# exBoard_3.net
KiCad netlist of a schematic drawn in EasyEDA Pro
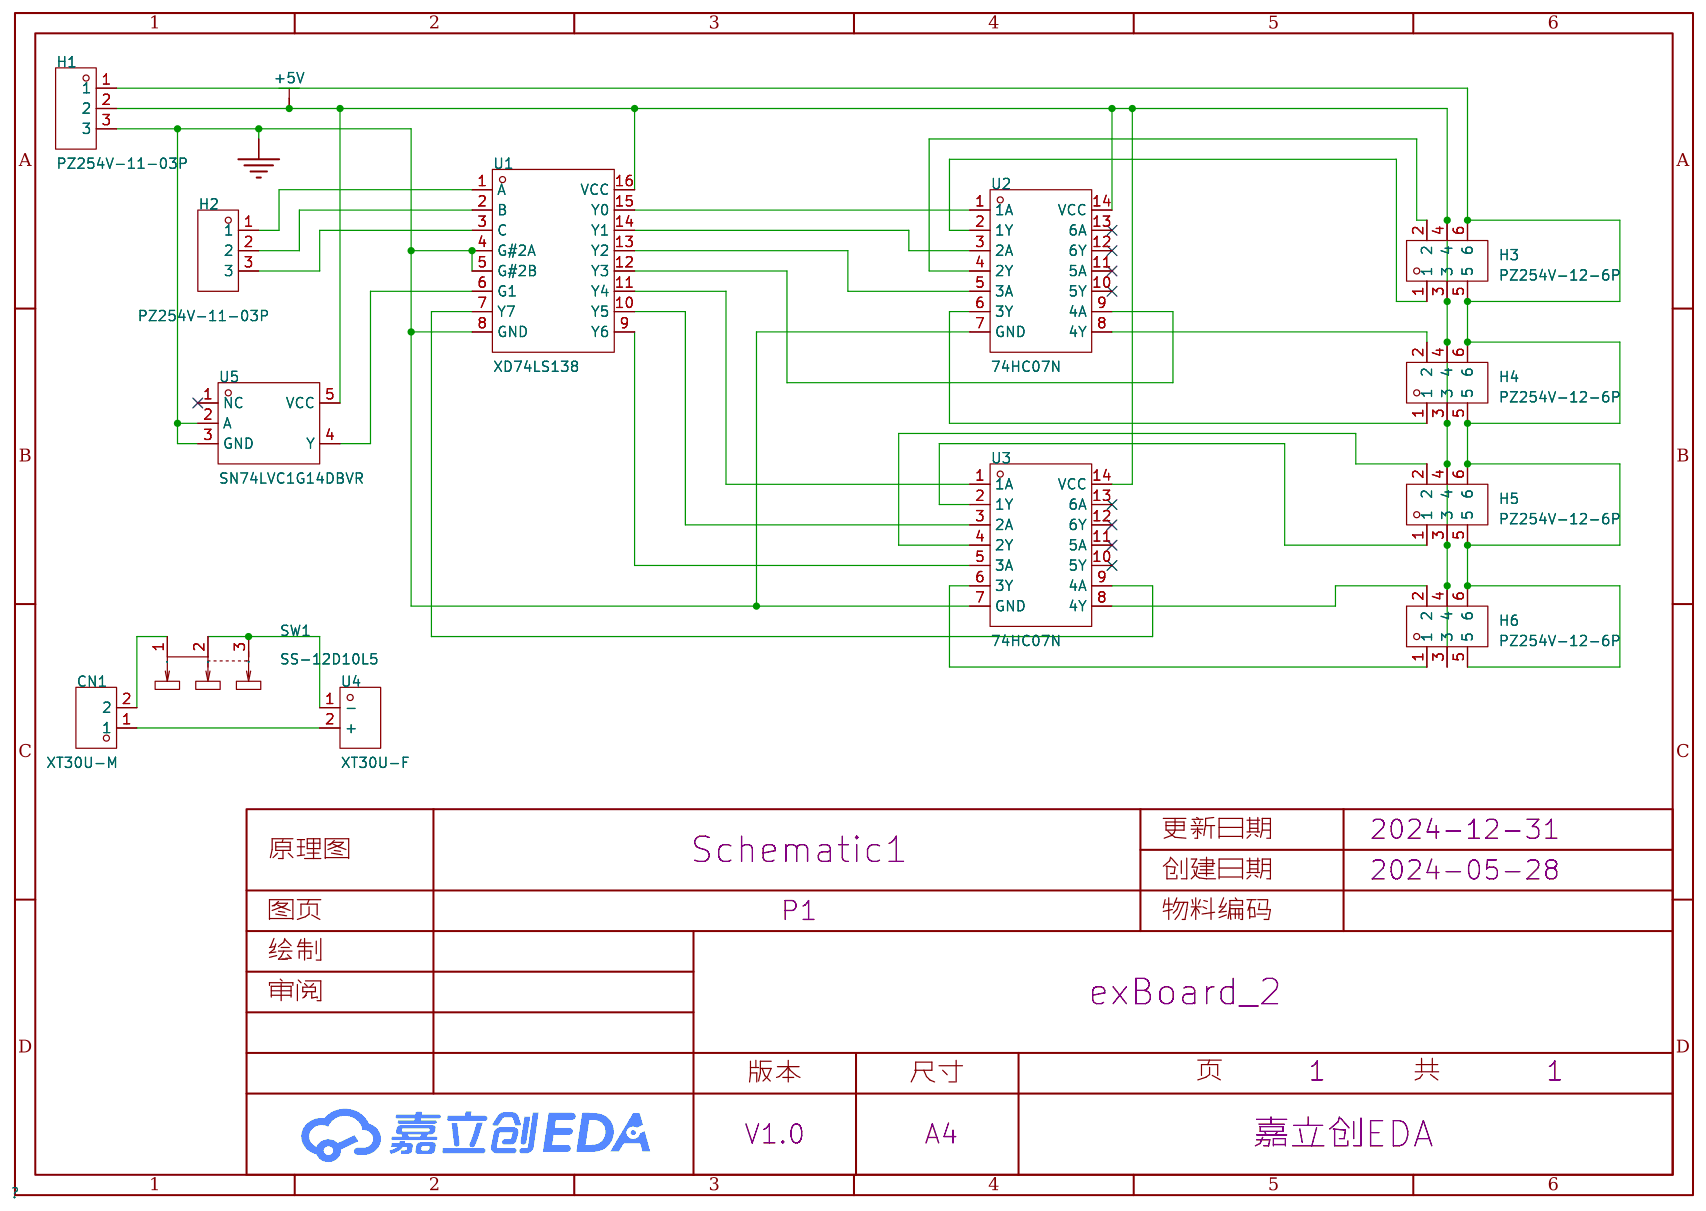
[diagram p0: schematic sheet]

(export (version "E")
  (design (tool "Eeschema 10.0.6"))
  (components
    (comp (ref "CN1")
      (value "XT30U-M")
      (footprint "easyedapro:CONN-TH_XT30U-M")
      (description "类别:-;类型1:-;")
      (fields (field (name "Manufacturer") "AMASS(艾迈斯)"))
      (libsource (lib "easyedapro") (part "XT30U-M"))
    )
    (comp (ref "H1")
      (value "PZ254V-11-03P")
      (footprint "easyedapro:HDR-TH_3P-P2.54-V-M")
      (fields (field (name "Manufacturer") "XFCN(兴飞)"))
      (libsource (lib "easyedapro") (part "PZ254V-11-03P_C2937625"))
    )
    (comp (ref "H2")
      (value "PZ254V-11-03P")
      (footprint "easyedapro:HDR-TH_3P-P2.54-V-M")
      (fields (field (name "Manufacturer") "XFCN(兴飞)"))
      (libsource (lib "easyedapro") (part "PZ254V-11-03P_C2937625"))
    )
    (comp (ref "H3")
      (value "PZ254V-12-6P")
      (footprint "easyedapro:HDR-TH_6P-P2.54-V-M-R2-C3-S2.54")
      (fields (field (name "Manufacturer") "XFCN(兴飞)"))
      (libsource (lib "easyedapro") (part "PZ254V-12-6P"))
    )
    (comp (ref "H4")
      (value "PZ254V-12-6P")
      (footprint "easyedapro:HDR-TH_6P-P2.54-V-M-R2-C3-S2.54")
      (fields (field (name "Manufacturer") "XFCN(兴飞)"))
      (libsource (lib "easyedapro") (part "PZ254V-12-6P"))
    )
    (comp (ref "H5")
      (value "PZ254V-12-6P")
      (footprint "easyedapro:HDR-TH_6P-P2.54-V-M-R2-C3-S2.54")
      (fields (field (name "Manufacturer") "XFCN(兴飞)"))
      (libsource (lib "easyedapro") (part "PZ254V-12-6P"))
    )
    (comp (ref "H6")
      (value "PZ254V-12-6P")
      (footprint "easyedapro:HDR-TH_6P-P2.54-V-M-R2-C3-S2.54")
      (fields (field (name "Manufacturer") "XFCN(兴飞)"))
      (libsource (lib "easyedapro") (part "PZ254V-12-6P"))
    )
    (comp (ref "SW1")
      (value "SS-12D10L5")
      (footprint "easyedapro:SW-TH_SS-12D10L5")
      (description "电路结构:单刀双掷;安装方式:直插;开关颜色:黑色;额定电流(DC):3A;额定电压(DC):125V;额定电流(AC):3A;额定电压(AC):125V;机械寿命:1万次;")
      (fields (field (name "Manufacturer") "XKB Connectivity(中国星坤)"))
      (libsource (lib "easyedapro") (part "SS-12D10L5"))
    )
    (comp (ref "U1")
      (value "XD74LS138")
      (footprint "easyedapro:DIP-16_L19.8-W6.5-P2.54-LS7.6-BL")
      (description "解码器/多路解器 低电平输出电流(IOL)：8mA 高电平输出电流(IOH)：400uA 供电电源：单电源 供电电压：4.75V~5.25V 3 线路到")
      (fields (field (name "Manufacturer") "XINLUDA(信路达)"))
      (libsource (lib "easyedapro") (part "XD74LS138"))
    )
    (comp (ref "U2")
      (value "74HC07N")
      (footprint "easyedapro:DIP-14_L19.4-W6.4-P2.54-LS7.6-BL")
      (fields (field (name "Manufacturer") "HGSEMI(华冠)"))
      (libsource (lib "easyedapro") (part "74HC07N"))
    )
    (comp (ref "U3")
      (value "74HC07N")
      (footprint "easyedapro:DIP-14_L19.4-W6.4-P2.54-LS7.6-BL")
      (fields (field (name "Manufacturer") "HGSEMI(华冠)"))
      (libsource (lib "easyedapro") (part "74HC07N"))
    )
    (comp (ref "U4")
      (value "XT30U-F")
      (footprint "easyedapro:CONN-TH_XT30U-F")
      (description "类别:-;类型1:-;")
      (fields (field (name "Manufacturer") "AMASS(艾迈斯)"))
      (libsource (lib "easyedapro") (part "XT30U-F"))
    )
    (comp (ref "U5")
      (value "SN74LVC1G14DBVR")
      (footprint "easyedapro:SOT-23-5_L3.0-W1.7-P0.95-LS2.8-BR")
      (description "输入类型:施密特触发器;电源电压:1.65V~5.5V;供电电流(最大值):10uA;电路数:1;最大传播延迟(tpd):20ns@5V,15pF;")
      (fields (field (name "Manufacturer") "UMW(友台半导体)"))
      (libsource (lib "easyedapro") (part "SN74LVC1G14DBVR_C434069"))
    )
  )
  (nets
    (net (code "1") (name "+5V") (class "Default")
      (node (ref "H1") (pin "2") (pinfunction "2_2") (pintype "unspecified"))
      (node (ref "H3") (pin "3") (pinfunction "3_3") (pintype "unspecified"))
      (node (ref "H3") (pin "4") (pinfunction "4_4") (pintype "unspecified"))
      (node (ref "H4") (pin "3") (pinfunction "3_3") (pintype "unspecified"))
      (node (ref "H4") (pin "4") (pinfunction "4_4") (pintype "unspecified"))
      (node (ref "H5") (pin "3") (pinfunction "3_3") (pintype "unspecified"))
      (node (ref "H5") (pin "4") (pinfunction "4_4") (pintype "unspecified"))
      (node (ref "H6") (pin "3") (pinfunction "3_3") (pintype "unspecified"))
      (node (ref "H6") (pin "4") (pinfunction "4_4") (pintype "unspecified"))
      (node (ref "U1") (pin "16") (pinfunction "VCC_16") (pintype "unspecified"))
      (node (ref "U2") (pin "14") (pinfunction "VCC_14") (pintype "unspecified"))
      (node (ref "U3") (pin "14") (pinfunction "VCC_14") (pintype "unspecified"))
      (node (ref "U5") (pin "5") (pinfunction "VCC_5") (pintype "unspecified"))
    )
    (net (code "2") (name "GND") (class "Default")
      (node (ref "H1") (pin "3") (pinfunction "3_3") (pintype "unspecified"))
      (node (ref "U1") (pin "4") (pinfunction "G#2A_4") (pintype "unspecified"))
      (node (ref "U1") (pin "5") (pinfunction "G#2B_5") (pintype "unspecified"))
      (node (ref "U1") (pin "8") (pinfunction "GND_8") (pintype "unspecified"))
      (node (ref "U2") (pin "7") (pinfunction "GND_7") (pintype "unspecified"))
      (node (ref "U3") (pin "7") (pinfunction "GND_7") (pintype "unspecified"))
      (node (ref "U5") (pin "2") (pinfunction "A_2") (pintype "unspecified"))
      (node (ref "U5") (pin "3") (pinfunction "GND_3") (pintype "unspecified"))
    )
    (net (code "3") (name "Net-(CN1-Pad2)") (class "Default")
      (node (ref "CN1") (pin "2") (pinfunction "2_2") (pintype "input"))
      (node (ref "SW1") (pin "1") (pinfunction "1_1") (pintype "unspecified"))
    )
    (net (code "4") (name "Net-(H1-Pad1)") (class "Default")
      (node (ref "H1") (pin "1") (pinfunction "1_1") (pintype "unspecified"))
      (node (ref "H3") (pin "5") (pinfunction "5_5") (pintype "unspecified"))
      (node (ref "H3") (pin "6") (pinfunction "6_6") (pintype "unspecified"))
      (node (ref "H4") (pin "5") (pinfunction "5_5") (pintype "unspecified"))
      (node (ref "H4") (pin "6") (pinfunction "6_6") (pintype "unspecified"))
      (node (ref "H5") (pin "5") (pinfunction "5_5") (pintype "unspecified"))
      (node (ref "H5") (pin "6") (pinfunction "6_6") (pintype "unspecified"))
      (node (ref "H6") (pin "5") (pinfunction "5_5") (pintype "unspecified"))
      (node (ref "H6") (pin "6") (pinfunction "6_6") (pintype "unspecified"))
    )
    (net (code "5") (name "Net-(U1-A)") (class "Default")
      (node (ref "H2") (pin "1") (pinfunction "1_1") (pintype "unspecified"))
      (node (ref "U1") (pin "1") (pinfunction "A_1") (pintype "unspecified"))
    )
    (net (code "6") (name "Net-(U1-B)") (class "Default")
      (node (ref "H2") (pin "2") (pinfunction "2_2") (pintype "unspecified"))
      (node (ref "U1") (pin "2") (pinfunction "B_2") (pintype "unspecified"))
    )
    (net (code "7") (name "Net-(U1-C)") (class "Default")
      (node (ref "H2") (pin "3") (pinfunction "3_3") (pintype "unspecified"))
      (node (ref "U1") (pin "3") (pinfunction "C_3") (pintype "unspecified"))
    )
    (net (code "8") (name "Net-(U1-G1)") (class "Default")
      (node (ref "U1") (pin "6") (pinfunction "G1_6") (pintype "unspecified"))
      (node (ref "U5") (pin "4") (pinfunction "Y_4") (pintype "unspecified"))
    )
    (net (code "9") (name "Net-(U1-Y0)") (class "Default")
      (node (ref "U1") (pin "15") (pinfunction "Y0_15") (pintype "unspecified"))
      (node (ref "U2") (pin "1") (pinfunction "1A_1") (pintype "unspecified"))
    )
    (net (code "10") (name "Net-(U1-Y1)") (class "Default")
      (node (ref "U1") (pin "14") (pinfunction "Y1_14") (pintype "unspecified"))
      (node (ref "U2") (pin "3") (pinfunction "2A_3") (pintype "unspecified"))
    )
    (net (code "11") (name "Net-(U1-Y2)") (class "Default")
      (node (ref "U1") (pin "13") (pinfunction "Y2_13") (pintype "unspecified"))
      (node (ref "U2") (pin "5") (pinfunction "3A_5") (pintype "unspecified"))
    )
    (net (code "12") (name "Net-(U1-Y3)") (class "Default")
      (node (ref "U1") (pin "12") (pinfunction "Y3_12") (pintype "unspecified"))
      (node (ref "U2") (pin "9") (pinfunction "4A_9") (pintype "unspecified"))
    )
    (net (code "13") (name "Net-(U1-Y4)") (class "Default")
      (node (ref "U1") (pin "11") (pinfunction "Y4_11") (pintype "unspecified"))
      (node (ref "U3") (pin "1") (pinfunction "1A_1") (pintype "unspecified"))
    )
    (net (code "14") (name "Net-(U1-Y5)") (class "Default")
      (node (ref "U1") (pin "10") (pinfunction "Y5_10") (pintype "unspecified"))
      (node (ref "U3") (pin "3") (pinfunction "2A_3") (pintype "unspecified"))
    )
    (net (code "15") (name "Net-(U1-Y6)") (class "Default")
      (node (ref "U1") (pin "9") (pinfunction "Y6_9") (pintype "unspecified"))
      (node (ref "U3") (pin "5") (pinfunction "3A_5") (pintype "unspecified"))
    )
    (net (code "16") (name "Net-(U1-Y7)") (class "Default")
      (node (ref "U1") (pin "7") (pinfunction "Y7_7") (pintype "unspecified"))
      (node (ref "U3") (pin "9") (pinfunction "4A_9") (pintype "unspecified"))
    )
    (net (code "17") (name "Net-(U2-1Y)") (class "Default")
      (node (ref "H3") (pin "1") (pinfunction "1_1") (pintype "unspecified"))
      (node (ref "U2") (pin "2") (pinfunction "1Y_2") (pintype "unspecified"))
    )
    (net (code "18") (name "Net-(U2-2Y)") (class "Default")
      (node (ref "H3") (pin "2") (pinfunction "2_2") (pintype "unspecified"))
      (node (ref "U2") (pin "4") (pinfunction "2Y_4") (pintype "unspecified"))
    )
    (net (code "19") (name "Net-(U2-3Y)") (class "Default")
      (node (ref "H4") (pin "1") (pinfunction "1_1") (pintype "unspecified"))
      (node (ref "U2") (pin "6") (pinfunction "3Y_6") (pintype "unspecified"))
    )
    (net (code "20") (name "Net-(U2-4Y)") (class "Default")
      (node (ref "H4") (pin "2") (pinfunction "2_2") (pintype "unspecified"))
      (node (ref "U2") (pin "8") (pinfunction "4Y_8") (pintype "unspecified"))
    )
    (net (code "21") (name "Net-(U3-1Y)") (class "Default")
      (node (ref "H5") (pin "1") (pinfunction "1_1") (pintype "unspecified"))
      (node (ref "U3") (pin "2") (pinfunction "1Y_2") (pintype "unspecified"))
    )
    (net (code "22") (name "Net-(U3-2Y)") (class "Default")
      (node (ref "H5") (pin "2") (pinfunction "2_2") (pintype "unspecified"))
      (node (ref "U3") (pin "4") (pinfunction "2Y_4") (pintype "unspecified"))
    )
    (net (code "23") (name "Net-(U3-3Y)") (class "Default")
      (node (ref "H6") (pin "1") (pinfunction "1_1") (pintype "unspecified"))
      (node (ref "U3") (pin "6") (pinfunction "3Y_6") (pintype "unspecified"))
    )
    (net (code "24") (name "Net-(U3-4Y)") (class "Default")
      (node (ref "H6") (pin "2") (pinfunction "2_2") (pintype "unspecified"))
      (node (ref "U3") (pin "8") (pinfunction "4Y_8") (pintype "unspecified"))
    )
    (net (code "25") (name "Net-(U4-+)") (class "Default")
      (node (ref "CN1") (pin "1") (pinfunction "1_1") (pintype "input"))
      (node (ref "U4") (pin "2") (pinfunction "+_2") (pintype "unspecified"))
    )
    (net (code "26") (name "Net-(U4--)") (class "Default")
      (node (ref "SW1") (pin "2") (pinfunction "2_2") (pintype "unspecified"))
      (node (ref "SW1") (pin "3") (pinfunction "3_3") (pintype "unspecified"))
      (node (ref "U4") (pin "1") (pinfunction "-_1") (pintype "unspecified"))
    )
    (net (code "27") (name "unconnected-(U2-5A-Pad11)") (class "Default")
      (node (ref "U2") (pin "11") (pinfunction "5A_11") (pintype "unspecified+no_connect"))
    )
    (net (code "28") (name "unconnected-(U2-5Y-Pad10)") (class "Default")
      (node (ref "U2") (pin "10") (pinfunction "5Y_10") (pintype "unspecified+no_connect"))
    )
    (net (code "29") (name "unconnected-(U2-6A-Pad13)") (class "Default")
      (node (ref "U2") (pin "13") (pinfunction "6A_13") (pintype "unspecified+no_connect"))
    )
    (net (code "30") (name "unconnected-(U2-6Y-Pad12)") (class "Default")
      (node (ref "U2") (pin "12") (pinfunction "6Y_12") (pintype "unspecified+no_connect"))
    )
    (net (code "31") (name "unconnected-(U3-5A-Pad11)") (class "Default")
      (node (ref "U3") (pin "11") (pinfunction "5A_11") (pintype "unspecified+no_connect"))
    )
    (net (code "32") (name "unconnected-(U3-5Y-Pad10)") (class "Default")
      (node (ref "U3") (pin "10") (pinfunction "5Y_10") (pintype "unspecified+no_connect"))
    )
    (net (code "33") (name "unconnected-(U3-6A-Pad13)") (class "Default")
      (node (ref "U3") (pin "13") (pinfunction "6A_13") (pintype "unspecified+no_connect"))
    )
    (net (code "34") (name "unconnected-(U3-6Y-Pad12)") (class "Default")
      (node (ref "U3") (pin "12") (pinfunction "6Y_12") (pintype "unspecified+no_connect"))
    )
    (net (code "35") (name "unconnected-(U5-NC-Pad1)") (class "Default")
      (node (ref "U5") (pin "1") (pinfunction "NC_1") (pintype "unspecified+no_connect"))
    )
  )
)
